# full_bridge.net
KiCad netlist of a schematic drawn in Altium Designer
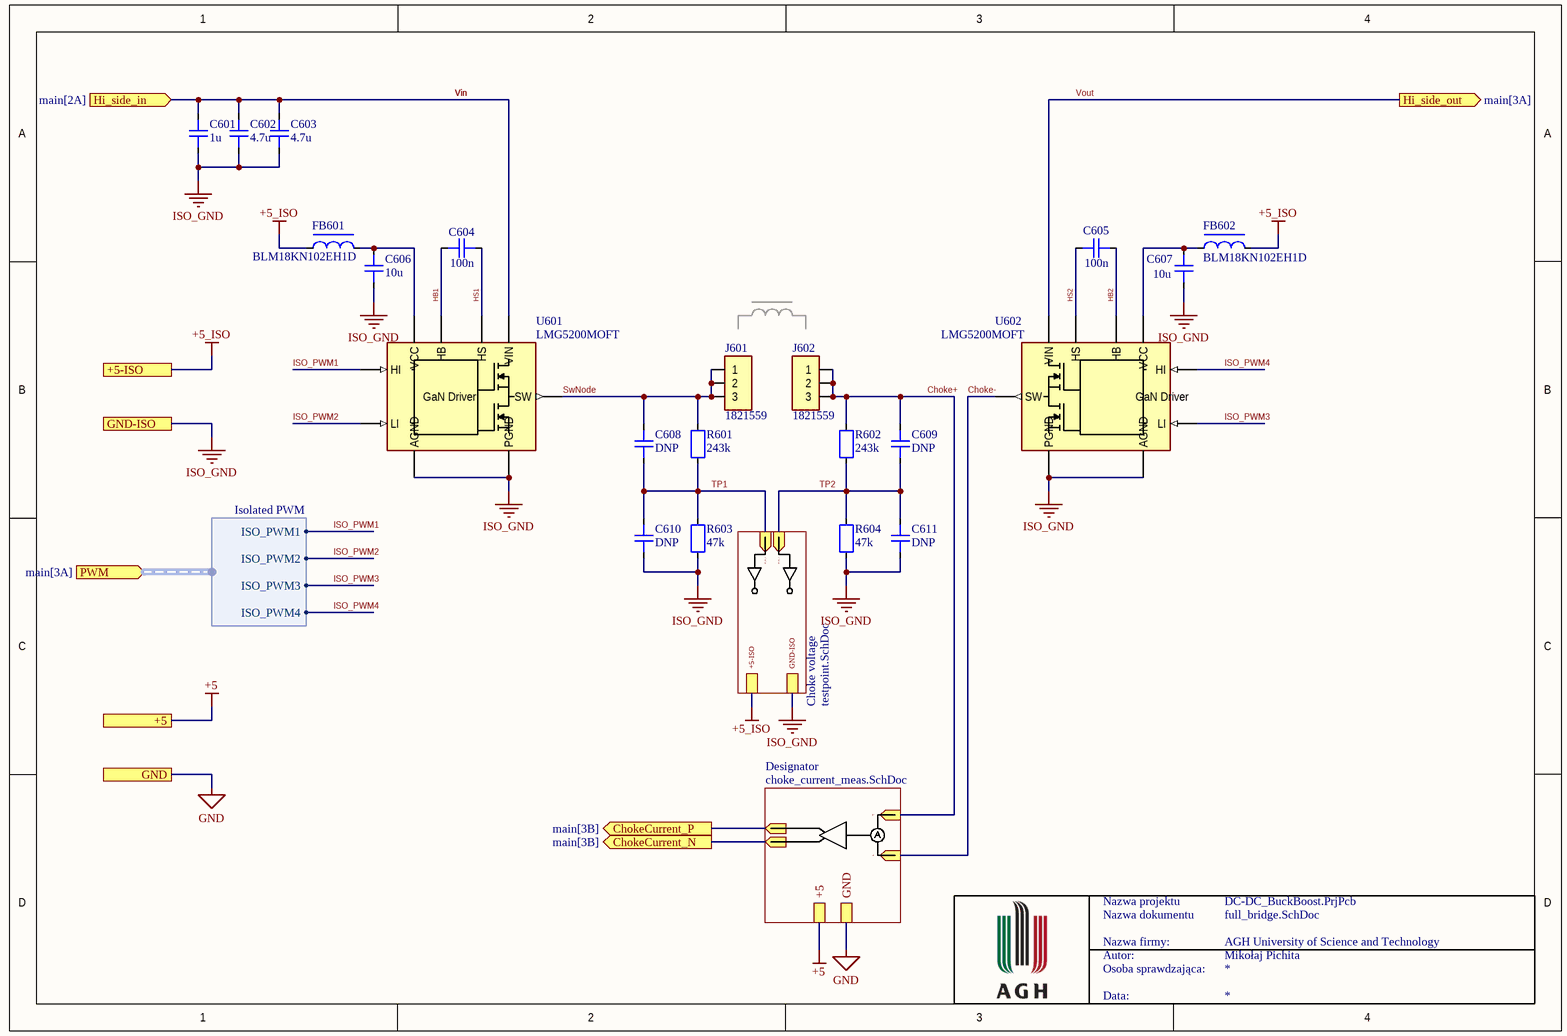
[diagram p0: full_bridge.SchDoc]

(export (version "E")
  (design (tool "Eeschema 10.0.6"))
  (components
    (comp (ref "C601")
      (value "1u")
      (footprint "CAP0603")
      (libsource (lib "schematic_library") (part "Capacitor"))
    )
    (comp (ref "C602")
      (value "4.7u")
      (footprint "CAP1206")
      (libsource (lib "schematic_library") (part "Capacitor"))
    )
    (comp (ref "C603")
      (value "4.7u")
      (footprint "CAP1206")
      (libsource (lib "schematic_library") (part "Capacitor"))
    )
    (comp (ref "C604")
      (value "100n")
      (footprint "CAP0603")
      (libsource (lib "schematic_library") (part "Capacitor"))
    )
    (comp (ref "C605")
      (value "100n")
      (footprint "CAP0603")
      (libsource (lib "schematic_library") (part "Capacitor"))
    )
    (comp (ref "C606")
      (value "10u")
      (footprint "CAP1206")
      (libsource (lib "schematic_library") (part "Capacitor"))
    )
    (comp (ref "C607")
      (value "10u")
      (footprint "CAP1206")
      (libsource (lib "schematic_library") (part "Capacitor"))
    )
    (comp (ref "C608")
      (value "DNP")
      (footprint "CAP0603")
      (libsource (lib "schematic_library") (part "Capacitor"))
    )
    (comp (ref "C609")
      (value "DNP")
      (footprint "CAP0603")
      (libsource (lib "schematic_library") (part "Capacitor"))
    )
    (comp (ref "C610")
      (value "DNP")
      (footprint "CAP0603")
      (libsource (lib "schematic_library") (part "Capacitor"))
    )
    (comp (ref "C611")
      (value "DNP")
      (footprint "CAP0603")
      (libsource (lib "schematic_library") (part "Capacitor"))
    )
    (comp (ref "FB601")
      (value "BLM18KN102EH1D")
      (footprint "RES0603")
      (libsource (lib "") (part "Ferrite Bead_1"))
    )
    (comp (ref "FB602")
      (value "BLM18KN102EH1D")
      (footprint "RES0603")
      (libsource (lib "schematic_library") (part "Ferrite Bead"))
    )
    (comp (ref "J601") (value "1821559") (footprint "1844882") (libsource (lib "") (part "1821559_1")))
    (comp (ref "J602")
      (value "1821559")
      (footprint "1844882")
      (libsource (lib "schematic_library") (part "1821559"))
    )
    (comp (ref "R601")
      (value "243k")
      (footprint "RES0603")
      (libsource (lib "schematic_library") (part "Resistor"))
    )
    (comp (ref "R602")
      (value "243k")
      (footprint "RES0603")
      (libsource (lib "schematic_library") (part "Resistor"))
    )
    (comp (ref "R603")
      (value "47k")
      (footprint "RES0603")
      (libsource (lib "schematic_library") (part "Resistor"))
    )
    (comp (ref "R604")
      (value "47k")
      (footprint "RES0603")
      (libsource (lib "schematic_library") (part "Resistor"))
    )
    (comp (ref "U601")
      (value "LMG5200MOFT")
      (footprint "FP-MOF0009A-MFG")
      (description "10-A GaN Half-Bridge Power Stage")
      (libsource (lib "") (part "LMG5200MOFT_1"))
    )
    (comp (ref "U602")
      (value "LMG5200MOFT")
      (footprint "FP-MOF0009A-MFG")
      (description "10-A GaN Half-Bridge Power Stage")
      (libsource (lib "schematic_library") (part "LMG5200MOFT"))
    )
  )
  (nets
    (net (code "4") (name "+5_ISO") (class "Default")
      (node (ref "FB601") (pin "1") (pintype "passive"))
      (node (ref "FB602") (pin "1") (pintype "passive"))
    )
    (net (code "5") (name "/Choke+") (class "Default")
      (node (ref "C609") (pin "1") (pintype "passive"))
      (node (ref "J602") (pin "1") (pinfunction "1_1") (pintype "passive"))
      (node (ref "J602") (pin "2") (pinfunction "2_2") (pintype "passive"))
      (node (ref "J602") (pin "3") (pinfunction "3_3") (pintype "passive"))
      (node (ref "R602") (pin "1") (pintype "passive"))
    )
    (net (code "6") (name "/Choke-") (class "Default")
      (node (ref "U602") (pin "8") (pinfunction "SW_8") (pintype "output"))
    )
    (net (code "9") (name "/HB1") (class "Default")
      (node (ref "C604") (pin "2") (pintype "passive"))
      (node (ref "U601") (pin "2") (pinfunction "HB_2") (pintype "passive"))
    )
    (net (code "10") (name "/HB2") (class "Default")
      (node (ref "C605") (pin "1") (pintype "passive"))
      (node (ref "U602") (pin "2") (pinfunction "HB_2") (pintype "passive"))
    )
    (net (code "11") (name "/HS1") (class "Default")
      (node (ref "C604") (pin "1") (pintype "passive"))
      (node (ref "U601") (pin "3") (pinfunction "HS_3") (pintype "passive"))
    )
    (net (code "12") (name "/HS2") (class "Default")
      (node (ref "C605") (pin "2") (pintype "passive"))
      (node (ref "U602") (pin "3") (pinfunction "HS_3") (pintype "passive"))
    )
    (net (code "13") (name "/ISO_PWM1") (class "Default")
      (node (ref "U601") (pin "4") (pinfunction "HI_4") (pintype "input"))
    )
    (net (code "14") (name "/ISO_PWM2") (class "Default")
      (node (ref "U601") (pin "5") (pinfunction "LI_5") (pintype "input"))
    )
    (net (code "15") (name "/ISO_PWM3") (class "Default")
      (node (ref "U602") (pin "5") (pinfunction "LI_5") (pintype "input"))
    )
    (net (code "16") (name "/ISO_PWM4") (class "Default")
      (node (ref "U602") (pin "4") (pinfunction "HI_4") (pintype "input"))
    )
    (net (code "17") (name "/SwNode") (class "Default")
      (node (ref "C608") (pin "1") (pintype "passive"))
      (node (ref "J601") (pin "1") (pinfunction "1_1") (pintype "passive"))
      (node (ref "J601") (pin "2") (pinfunction "2_2") (pintype "passive"))
      (node (ref "J601") (pin "3") (pinfunction "3_3") (pintype "passive"))
      (node (ref "R601") (pin "1") (pintype "passive"))
      (node (ref "U601") (pin "8") (pinfunction "SW_8") (pintype "output"))
    )
    (net (code "18") (name "/TP1") (class "Default")
      (node (ref "C608") (pin "2") (pintype "passive"))
      (node (ref "C610") (pin "1") (pintype "passive"))
      (node (ref "R601") (pin "2") (pintype "passive"))
      (node (ref "R603") (pin "1") (pintype "passive"))
    )
    (net (code "19") (name "/TP2") (class "Default")
      (node (ref "C609") (pin "2") (pintype "passive"))
      (node (ref "C611") (pin "1") (pintype "passive"))
      (node (ref "R602") (pin "2") (pintype "passive"))
      (node (ref "R604") (pin "1") (pintype "passive"))
    )
    (net (code "20") (name "/Vin") (class "Default")
      (node (ref "C601") (pin "1") (pintype "passive"))
      (node (ref "C602") (pin "1") (pintype "passive"))
      (node (ref "C603") (pin "1") (pintype "passive"))
      (node (ref "U601") (pin "1") (pinfunction "VIN_1") (pintype "passive"))
    )
    (net (code "21") (name "/Vout") (class "Default")
      (node (ref "U602") (pin "1") (pinfunction "VIN_1") (pintype "passive"))
    )
    (net (code "24") (name "ISO_GND") (class "Default")
      (node (ref "C601") (pin "2") (pintype "passive"))
      (node (ref "C602") (pin "2") (pintype "passive"))
      (node (ref "C603") (pin "2") (pintype "passive"))
      (node (ref "C606") (pin "2") (pintype "passive"))
      (node (ref "C607") (pin "1") (pintype "passive"))
      (node (ref "C610") (pin "2") (pintype "passive"))
      (node (ref "C611") (pin "2") (pintype "passive"))
      (node (ref "R603") (pin "2") (pintype "passive"))
      (node (ref "R604") (pin "2") (pintype "passive"))
      (node (ref "U601") (pin "7") (pinfunction "AGND_7") (pintype "power_in"))
      (node (ref "U601") (pin "9") (pinfunction "PGND_9") (pintype "power_in"))
      (node (ref "U602") (pin "7") (pinfunction "AGND_7") (pintype "power_in"))
      (node (ref "U602") (pin "9") (pinfunction "PGND_9") (pintype "power_in"))
    )
    (net (code "25") (name "Net-(U601-VCC)") (class "Default")
      (node (ref "C606") (pin "1") (pintype "passive"))
      (node (ref "FB601") (pin "2") (pintype "passive"))
      (node (ref "U601") (pin "6") (pinfunction "VCC_6") (pintype "power_in"))
    )
    (net (code "26") (name "Net-(U602-VCC)") (class "Default")
      (node (ref "C607") (pin "2") (pintype "passive"))
      (node (ref "FB602") (pin "2") (pintype "passive"))
      (node (ref "U602") (pin "6") (pinfunction "VCC_6") (pintype "power_in"))
    )
  )
)
